# PowerManagementModule.net
KiCad netlist of a schematic drawn in Altium Designer
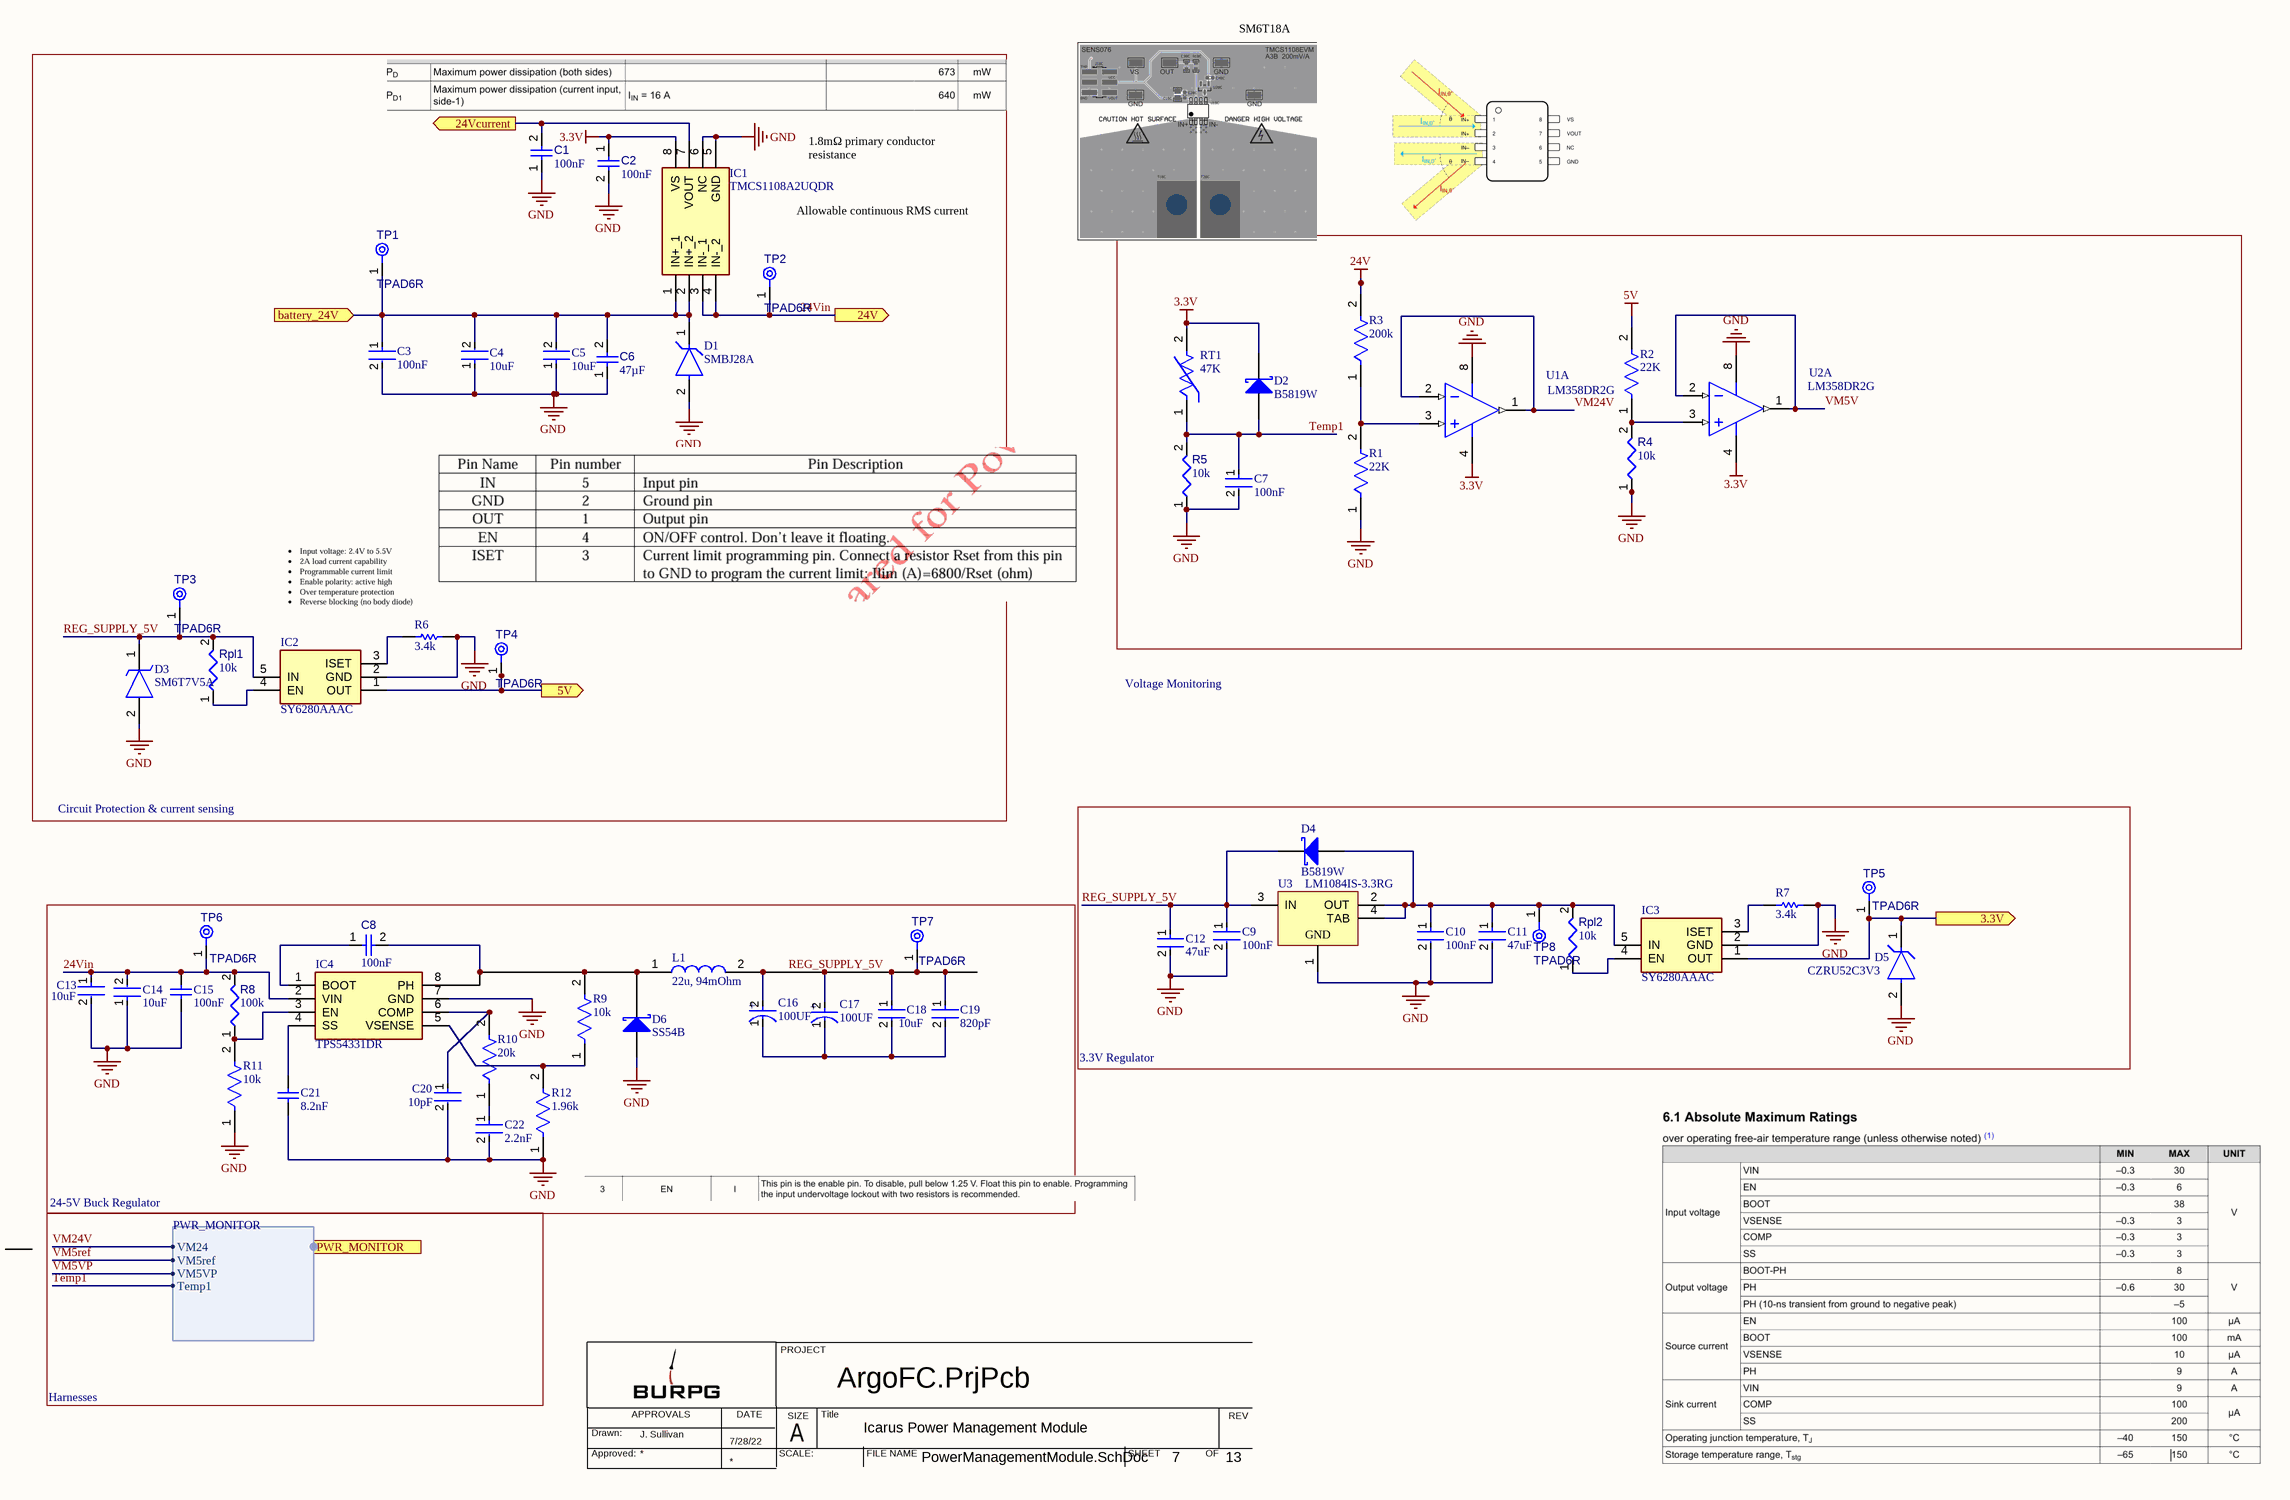
[diagram p0: PowerManagementModule.SchDoc]

(export (version "E")
  (design (tool "Eeschema 10.0.6"))
  (components
    (comp (ref "C1")
      (value "100nF")
      (footprint "CAPC1005X56X25LL10T15")
      (description "Chip Capacitor, 0.1 uF, +/- 5%, 16 V, 0402 (1005 Metric)")
      (fields (field (name "TOLERANCE") "5%") (field (name "Comment") "Capacitor 0.1 uF +/- 5% 16 V 0402"))
      (libsource (lib "Yuxuan chen") (part "CAP-NP-2"))
    )
    (comp (ref "C2")
      (value "100nF")
      (footprint "CAPC1005X56X25LL10T15")
      (description "Chip Capacitor, 0.1 uF, +/- 5%, 16 V, 0402 (1005 Metric)")
      (fields (field (name "TOLERANCE") "5%") (field (name "Comment") "Capacitor 0.1 uF +/- 5% 16 V 0402"))
      (libsource (lib "Yuxuan chen") (part "CAP-NP-2"))
    )
    (comp (ref "C3")
      (value "100nF")
      (footprint "FP-CGA3E-0_3-0_1-IPC_A")
      (description "Cap Ceramic 100nF 50V X7R 10% Pad SMD 0603 +125°C Automotive T/R")
      (fields (field (name "TOLERANCE") "10%") (field (name "VOLTAGE") "50V"))
      (libsource (lib "Altium Content Vault") (part "b4654b650e69147ec39a6b967a45e02"))
    )
    (comp (ref "C4")
      (value "10uF")
      (footprint "FP-GRM31-0_2-MFG")
      (description "CAP CER 10UF 50V X5R 1206")
      (fields
        (field (name "OCTOPART") "https://octopart.com/grm31cr61h106ka12l-murata-18903335")
        (field (name "TOLERANCE") "10%")
      )
      (libsource (lib "Altium Content Vault") (part "11868f565c42a9108669ba33697ecf6"))
    )
    (comp (ref "C5")
      (value "10uF")
      (footprint "FP-GRM31-0_2-MFG")
      (description "CAP CER 10UF 50V X5R 1206")
      (fields
        (field (name "OCTOPART") "https://octopart.com/grm31cr61h106ka12l-murata-18903335")
        (field (name "TOLERANCE") "10%")
      )
      (libsource (lib "Altium Content Vault") (part "11868f565c42a9108669ba33697ecf6"))
    )
    (comp (ref "C6")
      (value "47µF")
      (footprint "CAPC0805(2012)145_L")
      (description "Chip Capacitor, 47µF +/-40%, 50V, 0805, Thickness 1.45 mm")
      (fields (field (name "TOLERANCE") "10%") (field (name "Comment") "Capacitor 47µF +/-40% 6.3V 0805"))
      (libsource (lib "Yuxuan chen") (part "CAP-NP-2"))
    )
    (comp (ref "C7")
      (value "100nF")
      (footprint "FP-CGA3E-0_3-0_1-IPC_A")
      (description "Cap Ceramic 100nF 50V X7R 10% Pad SMD 0603 +125°C Automotive T/R")
      (fields (field (name "TOLERANCE") "10%") (field (name "VOLTAGE") "50V"))
      (libsource (lib "Altium Content Vault") (part "b4654b650e69147ec39a6b967a45e02"))
    )
    (comp (ref "C8")
      (value "100nF")
      (footprint "CAPC1608X90X40NL10T20")
      (description "Chip Capacitor, 100 nF, +/- 10%, 50 V, 0603 (1608 Metric)")
      (fields (field (name "TOLERANCE") "10%") (field (name "Comment") "Capacitor 100 nF +/-10% 50 V 0603"))
      (libsource (lib "Yuxuan chen") (part "CAP-NP-2"))
    )
    (comp (ref "C9")
      (value "100nF")
      (footprint "FP-CGA3E-0_3-0_1-IPC_A")
      (description "Cap Ceramic 100nF 50V X7R 10% Pad SMD 0603 +125°C Automotive T/R")
      (fields (field (name "TOLERANCE") "10%") (field (name "VOLTAGE") "50V"))
      (libsource (lib "Altium Content Vault") (part "b4654b650e69147ec39a6b967a45e02"))
    )
    (comp (ref "C10")
      (value "100nF")
      (footprint "FP-CGA3E-0_3-0_1-IPC_A")
      (description "Cap Ceramic 100nF 50V X7R 10% Pad SMD 0603 +125°C Automotive T/R")
      (fields (field (name "TOLERANCE") "10%") (field (name "VOLTAGE") "50V"))
      (libsource (lib "Altium Content Vault") (part "b4654b650e69147ec39a6b967a45e02"))
    )
    (comp (ref "C11")
      (value "47uF")
      (footprint "FP-C1210C476M4PACTU-MFG")
      (description "CAP CER 47UF 16V X5R 1210")
      (fields (field (name "TOLERANCE") "20%") (field (name "VOLTAGE") "16V"))
      (libsource (lib "Altium Content Vault") (part "02cd4be3c70576c341d710602a673aa"))
    )
    (comp (ref "C12")
      (value "47uF")
      (footprint "FP-C1210C476M4PACTU-MFG")
      (description "CAP CER 47UF 16V X5R 1210")
      (fields (field (name "TOLERANCE") "20%") (field (name "VOLTAGE") "16V"))
      (libsource (lib "Altium Content Vault") (part "02cd4be3c70576c341d710602a673aa"))
    )
    (comp (ref "C13")
      (value "10uF")
      (footprint "FP-GRM31-0_2-MFG")
      (description "CAP CER 10UF 50V X5R 1206")
      (fields
        (field (name "OCTOPART") "https://octopart.com/grm31cr61h106ka12l-murata-18903335")
        (field (name "TOLERANCE") "10%")
      )
      (libsource (lib "Altium Content Vault") (part "11868f565c42a9108669ba33697ecf6"))
    )
    (comp (ref "C14")
      (value "10uF")
      (footprint "FP-GRM31-0_2-MFG")
      (description "CAP CER 10UF 50V X5R 1206")
      (fields
        (field (name "OCTOPART") "https://octopart.com/grm31cr61h106ka12l-murata-18903335")
        (field (name "TOLERANCE") "10%")
      )
      (libsource (lib "Altium Content Vault") (part "11868f565c42a9108669ba33697ecf6"))
    )
    (comp (ref "C15")
      (value "100nF")
      (footprint "CAPC2013X100X50NL20T25")
      (description "C0805F103K5RACTU 10000 pF ±10% 50V Ceramic Capacitor X7R 0805 (2012 Metric)")
      (fields (field (name "PART NUMBER") "C0805F103K5RACTU") (field (name "MANUFACTURER") "Kemet"))
      (libsource (lib "Altium Content Vault") (part "CAP"))
    )
    (comp (ref "C16")
      (value "100UF")
      (footprint "FP-TPSC-MFG")
      (description "CAP TANT 100UF 10% 25V 2312")
      (fields (field (name "VOLTAGE") "10V") (field (name "TOLERANCE") "10%"))
      (libsource (lib "Altium Content Vault") (part "cf48714ba7e38822c1575c7ec0b6d1f"))
    )
    (comp (ref "C17")
      (value "100UF")
      (footprint "FP-TPSC-MFG")
      (description "CAP TANT 100UF 10% 25V 2312")
      (fields (field (name "VOLTAGE") "10V") (field (name "TOLERANCE") "10%"))
      (libsource (lib "Altium Content Vault") (part "cf48714ba7e38822c1575c7ec0b6d1f"))
    )
    (comp (ref "C18")
      (value "10uF")
      (footprint "FP-GRM21B-0_1-IPC_C")
      (description "Chip Multilayer Ceramic Capacitors for General Purpose, 0805, 10uF, X5R, 15%, 10%, 25V")
      (fields (field (name "TOLERANCE") "10%") (field (name "VOLTAGE") "16V"))
      (libsource (lib "Altium Content Vault") (part "b4654b650e69147ec39a6b967a45e02"))
    )
    (comp (ref "C19")
      (value "820pF")
      (footprint "FP-C0603C-CF-MFG")
      (description "C0603C 820pF Ceramic Multilayer Capacitor; 50 VDC; +125degC; X7R Dielec; +/-10%")
      (fields
        (field (name "TOLERANCE") "0.1")
        (field (name "OCTOPART") "https://octopart.com/c0603c821k5ractu-kemet-129686")
      )
      (libsource (lib "Altium Content Vault") (part "b4654b650e69147ec39a6b967a45e02"))
    )
    (comp (ref "C20")
      (value "10pF")
      (footprint "FP-C0805C-DN-MFG")
      (description "CAP CER 10PF 50V 10% NP0 0805C0805C100K5GACTU")
      (fields
        (field (name "MANUFACTURER PART NUMBER") "C0805C100K5GACTU")
        (field (name "MANUFACTURER") "KEMET")
      )
      (libsource (lib "Altium Content Vault") (part "b4654b650e69147ec39a6b967a45e02"))
    )
    (comp (ref "C21")
      (value "8.2nF")
      (footprint "CAPC1005X55X25NL05T10")
      (description "GRM155R71C822KA01D 0402  8.2nF")
      (fields (field (name "PART NUMBER") "GRM155R71C822KA01D") (field (name "MANUFACTURER") "Murata"))
      (libsource (lib "Altium Content Vault") (part "CAP"))
    )
    (comp (ref "C22")
      (value "2.2nF")
      (footprint "FP-CL21-IPC_C")
      (description "CL21 Series 0805 2.2nF 50V ±5% Tolerance C0G Multilayer Ceramic Chip Capacitor CL21C222JBFNNNE")
      (fields (field (name "TOLERANCE") "5%") (field (name "VOLTAGE") "50V"))
      (libsource (lib "Altium Content Vault") (part "b4654b650e69147ec39a6b967a45e02"))
    )
    (comp (ref "D1")
      (value "SMBJ28A")
      (footprint "FP-SMBJ-MFG")
      (description "TVS DIODE 28V 45.4V DO214AA")
      (fields
        (field (name "MANUFACTURER") "Littelfuse Inc")
        (field (name "OCTOPART") "https://octopart.com/smbj28a-littelfuse-350790")
      )
      (libsource (lib "Altium Content Vault") (part "f813f71cba58e380607f5dd3caf9714"))
    )
    (comp (ref "D2")
      (value "B5819W")
      (footprint "MCC-SOD123_V")
      (description "Schottky Barrier Rectifier, 40 V, 1 A, -65 to 125 degC, 2-Pin SOD123, RoHS, Tape and Reel")
      (fields (field (name "MANUFACTURER") "Micro Commercial Components"))
      (libsource (lib "Yuxuan chen") (part "DSKY-AK-2"))
    )
    (comp (ref "D3")
      (value "SM6T7V5A")
      (footprint "SamacSys:DIOM5436X265N")
      (description "TVS Diode (Uni-directional)")
      (fields (field (name "MOUSER PART NUMBER") "511-SM6T7V5A"))
      (libsource (lib "*") (part "SM6T7V5A"))
    )
    (comp (ref "D4")
      (value "B5819W")
      (footprint "MCC-SOD123_V")
      (description "Schottky Barrier Rectifier, 40 V, 1 A, -65 to 125 degC, 2-Pin SOD123, RoHS, Tape and Reel")
      (fields (field (name "MANUFACTURER") "Micro Commercial Components"))
      (libsource (lib "Yuxuan chen") (part "DSKY-AK-2"))
    )
    (comp (ref "D5")
      (value "CZRU52C3V3")
      (footprint "FP-0603-SOD-523F-MFG")
      (description "DIODE ZENER 3.3V 150MW 0603")
      (fields (field (name "TOLERANCE") "5%"))
      (libsource (lib "Altium Content Vault") (part "f813f71cba58e380607f5dd3caf9714"))
    )
    (comp (ref "D6")
      (value "SS54B")
      (footprint "JCET-SMB-2_M")
      (description "Schottky Barrier Rectifier, 40 V, 5 A, -55 to 150 degC, 2-Pin SMD")
      (fields (field (name "MANUFACTURER") "JCET"))
      (libsource (lib "Yuxuan chen") (part "DSKY-AK-2"))
    )
    (comp (ref "IC1")
      (value "TMCS1108A2UQDR")
      (footprint "SamacSys:SOIC127P600X175-8N")
      (fields (field (name "MOUSER PART NUMBER") "595-TMCS1108A2UQDR"))
      (libsource (lib "*") (part "TMCS1108A2UQDR"))
    )
    (comp (ref "IC2")
      (value "SY6280AAAC")
      (footprint "SamacSys:SOT95P285X140-5N")
      (description "Integrated Circuit")
      (libsource (lib "*") (part "SY6280AAAC"))
    )
    (comp (ref "IC3")
      (value "SY6280AAAC")
      (footprint "SamacSys:SOT95P285X140-5N")
      (description "Integrated Circuit")
      (libsource (lib "*") (part "SY6280AAAC"))
    )
    (comp (ref "IC4")
      (value "TPS54331DR")
      (footprint "SamacSys:SOIC127P600X175-8N")
      (description "Integrated Circuit")
      (fields (field (name "MOUSER PART NUMBER") "595-TPS54331DR"))
      (libsource (lib "*") (part "TPS54331DR"))
    )
    (comp (ref "L1")
      (value "22u, 94mOhm")
      (footprint "SamacSys:INDPM8682X400N")
      (description "Inductor， IHLP3232DZER220M11, 3.3A sat")
      (fields
        (field (name "MANUFACTURER_PART_NUMBER") "IHLP3232DZER220M11")
        (field (name "MOUSER PART NUMBER") "70-IHLP3232DZER220M1")
      )
      (libsource (lib "*") (part "IHLP3232DZER220M11"))
    )
    (comp (ref "R1")
      (value "22K")
      (footprint "FP-CRCW0603-e3-IPC_B")
      (description "RES Thick Film, 22kΩ, 1%, 0.1W, 100ppm/°C, 0603")
      (fields (field (name "TOLERANCE") "1%"))
      (libsource (lib "Altium Content Vault") (part "1029c3af85768c4190bb7ad29bc67b5"))
    )
    (comp (ref "R2")
      (value "22K")
      (footprint "FP-CRCW0603-e3-IPC_B")
      (description "RES Thick Film, 22kΩ, 1%, 0.1W, 100ppm/°C, 0603")
      (fields (field (name "TOLERANCE") "1%"))
      (libsource (lib "Altium Content Vault") (part "1029c3af85768c4190bb7ad29bc67b5"))
    )
    (comp (ref "R3")
      (value "200k")
      (footprint "FP-RC0603-0_55-IPC_B")
      (description "RES SMD 200K OHM 1% 1/10W 0603")
      (fields (field (name "TOLERANCE") "1%"))
      (libsource (lib "Altium Content Vault") (part "1029c3af85768c4190bb7ad29bc67b5"))
    )
    (comp (ref "R4")
      (value "10k")
      (footprint "RESC0402(1005)_L")
      (description "10K 0.063W 1% 0402 (1005 Metric)  SMD")
      (fields (field (name "POWER") "63mW") (field (name "TOLERANCE") "1%"))
      (libsource (lib "Yuxuan chen") (part "10KR2F"))
    )
    (comp (ref "R5")
      (value "10k")
      (footprint "RESC0402(1005)_L")
      (description "10K 0.063W 1% 0402 (1005 Metric)  SMD")
      (fields (field (name "POWER") "63mW") (field (name "TOLERANCE") "1%"))
      (libsource (lib "Yuxuan chen") (part "10KR2F"))
    )
    (comp (ref "R6")
      (value "3.4k")
      (footprint "RESC1609X50X30LL10T20")
      (fields (field (name "MANUFACTURER") "Vishay Dale") (field (name "PART NUMBER") "CRCW06033K40FKEA"))
      (libsource (lib "Altium Content Vault") (part "RES"))
    )
    (comp (ref "R7")
      (value "3.4k")
      (footprint "RESC1609X50X30LL10T20")
      (fields (field (name "MANUFACTURER") "Vishay Dale") (field (name "PART NUMBER") "CRCW06033K40FKEA"))
      (libsource (lib "Altium Content Vault") (part "RES"))
    )
    (comp (ref "R8")
      (value "100k")
      (footprint "RESC1608X55X25ML10T15")
      (description "Chip Resistor, 100 KOhm, +/- 1%, 0.1 W, -55 to 155 degC, 0603 (1608 Metric)")
      (fields (field (name "TOLERANCE") "1%") (field (name "POWER") "100mW"))
      (libsource (lib "Yuxuan chen") (part "RES-2"))
    )
    (comp (ref "R9")
      (value "10k")
      (footprint "FP-CRCW0805-e3-IPC_A")
      (description "RES Thick Film, 10kΩ, 1%, 0.125W, 100ppm/°C, 0805")
      (fields (field (name "TOLERANCE") "1%"))
      (libsource (lib "Altium Content Vault") (part "1029c3af85768c4190bb7ad29bc67b5"))
    )
    (comp (ref "R10")
      (value "20k")
      (footprint "FP-CRCW0402-e3-IPC_B")
      (description "RES Thick Film, 20kΩ, 1%, 0.063W, 100ppm/°C, 0402")
      (fields (field (name "TOLERANCE") "1%"))
      (libsource (lib "Altium Content Vault") (part "1029c3af85768c4190bb7ad29bc67b5"))
    )
    (comp (ref "R11")
      (value "10k")
      (footprint "FP-CRCW0805-e3-IPC_A")
      (description "RES Thick Film, 10kΩ, 1%, 0.125W, 100ppm/°C, 0805")
      (fields (field (name "TOLERANCE") "1%"))
      (libsource (lib "Altium Content Vault") (part "1029c3af85768c4190bb7ad29bc67b5"))
    )
    (comp (ref "R12")
      (value "1.96k")
      (footprint "FP-CRCW0402-e3-MFG")
      (description "CRCW04021K96FKED  RES Thick Film, 1.96kΩ, 1%, 0.063W, 100ppm/°C, 0402")
      (fields (field (name "TOLERANCE") "1%"))
      (libsource (lib "Altium Content Vault") (part "1029c3af85768c4190bb7ad29bc67b5"))
    )
    (comp (ref "Rpl1")
      (value "10k")
      (footprint "RESC0402(1005)_L")
      (description "10K 0.063W 1% 0402 (1005 Metric)  SMD")
      (fields (field (name "POWER") "63mW") (field (name "TOLERANCE") "1%"))
      (libsource (lib "Yuxuan chen") (part "10KR2F"))
    )
    (comp (ref "Rpl2")
      (value "10k")
      (footprint "RESC0402(1005)_L")
      (description "10K 0.063W 1% 0402 (1005 Metric)  SMD")
      (fields (field (name "POWER") "63mW") (field (name "TOLERANCE") "1%"))
      (libsource (lib "Yuxuan chen") (part "10KR2F"))
    )
    (comp (ref "RT1")
      (value "47K")
      (footprint "FP-NCP18-0_15-IPC_A")
      (description "NTC Thermistor for Temperature Sensor, 0603, 47kΩ, 5%, 0.046mA, 5V")
      (fields (field (name "TOLERANCE") "5%"))
      (libsource (lib "Altium Content Vault") (part "3b148a6ebabc5fb4d708a66c052d352"))
    )
    (comp (ref "TP1")
      (value "TPAD6R")
      (footprint "TP06R")
      (description "0.6mm round")
      (libsource (lib "Yuxuan chen") (part "CMP-001-0001-4"))
    )
    (comp (ref "TP2")
      (value "TPAD6R")
      (footprint "TP06R")
      (description "0.6mm round")
      (libsource (lib "Yuxuan chen") (part "CMP-001-0001-4"))
    )
    (comp (ref "TP3")
      (value "TPAD6R")
      (footprint "TP06R")
      (description "0.6mm round")
      (libsource (lib "Yuxuan chen") (part "CMP-001-0001-4"))
    )
    (comp (ref "TP4")
      (value "TPAD6R")
      (footprint "TP06R")
      (description "0.6mm round")
      (libsource (lib "Yuxuan chen") (part "CMP-001-0001-4"))
    )
    (comp (ref "TP5")
      (value "TPAD6R")
      (footprint "TP06R")
      (description "0.6mm round")
      (libsource (lib "Yuxuan chen") (part "CMP-001-0001-4"))
    )
    (comp (ref "TP6")
      (value "TPAD6R")
      (footprint "TP06R")
      (description "0.6mm round")
      (libsource (lib "Yuxuan chen") (part "CMP-001-0001-4"))
    )
    (comp (ref "TP7")
      (value "TPAD6R")
      (footprint "TP06R")
      (description "0.6mm round")
      (libsource (lib "Yuxuan chen") (part "CMP-001-0001-4"))
    )
    (comp (ref "TP8")
      (value "TPAD6R")
      (footprint "TP06R")
      (description "0.6mm round")
      (libsource (lib "Yuxuan chen") (part "CMP-001-0001-4"))
    )
    (comp (ref "U1")
      (value "LM358DR2G")
      (footprint "ONSC-SOIC-8-751-07_V")
      (fields (field (name "MANUFACTURER") "ON Semiconductor"))
      (libsource (lib "Yuxuan chen") (part "ONSC-LM258_2904-8"))
    )
    (comp (ref "U2")
      (value "LM358DR2G")
      (footprint "ONSC-SOIC-8-751-07_V")
      (fields (field (name "MANUFACTURER") "ON Semiconductor"))
      (libsource (lib "Yuxuan chen") (part "ONSC-LM258_2904-8"))
    )
    (comp (ref "U3")
      (value "LM1084IS-3.3RG")
      (footprint "KTT0003B_N")
      (description "5A Low Dropout Positive Regulators, 3-pin TO-263, Pb-Free")
      (fields
        (field (name "PARTNUMBER") "LM1084IS-3.3/NOPB")
        (field (name "MANUFACTURER") "Texas Instruments")
      )
      (libsource (lib "Altium Content Vault") (part "PM-REG-LM1086-SOT4"))
    )
  )
  (nets
    (net (code "2") (name "/24Vcurrent") (class "Default")
      (node (ref "C1") (pin "2") (pinfunction "2_2") (pintype "passive"))
      (node (ref "IC1") (pin "7") (pinfunction "VOUT_7") (pintype "passive"))
    )
    (net (code "3") (name "/REG_SUPPLY_5V") (class "Default")
      (node (ref "C12") (pin "1") (pinfunction "1_1") (pintype "passive"))
      (node (ref "C16") (pin "2") (pinfunction "A_2") (pintype "passive"))
      (node (ref "C17") (pin "2") (pinfunction "A_2") (pintype "passive"))
      (node (ref "C18") (pin "1") (pinfunction "1_1") (pintype "passive"))
      (node (ref "C19") (pin "1") (pinfunction "1_1") (pintype "passive"))
      (node (ref "C9") (pin "1") (pinfunction "1_1") (pintype "passive"))
      (node (ref "D3") (pin "1") (pinfunction "K_1") (pintype "passive"))
      (node (ref "D4") (pin "2") (pinfunction "K_2") (pintype "passive"))
      (node (ref "IC2") (pin "5") (pinfunction "IN_5") (pintype "passive"))
      (node (ref "L1") (pin "2") (pinfunction "2_2") (pintype "passive"))
      (node (ref "Rpl1") (pin "2") (pinfunction "2_2") (pintype "passive"))
      (node (ref "TP3") (pin "1") (pinfunction "TP_1") (pintype "passive"))
      (node (ref "TP7") (pin "1") (pinfunction "TP_1") (pintype "passive"))
      (node (ref "U3") (pin "3") (pinfunction "IN_3") (pintype "power_in"))
    )
    (net (code "4") (name "/Temp1") (class "Default")
      (node (ref "C7") (pin "1") (pinfunction "1_1") (pintype "passive"))
      (node (ref "D2") (pin "1") (pinfunction "A_1") (pintype "passive"))
      (node (ref "R5") (pin "2") (pinfunction "2_2") (pintype "passive"))
      (node (ref "RT1") (pin "1") (pinfunction "1_1") (pintype "passive"))
    )
    (net (code "5") (name "/VM5V") (class "Default")
      (node (ref "U2") (pin "1") (pinfunction "OUTA_1") (pintype "output"))
      (node (ref "U2") (pin "2") (pinfunction "INA-_2") (pintype "input"))
    )
    (net (code "8") (name "/VM24V") (class "Default")
      (node (ref "U1") (pin "1") (pinfunction "OUTA_1") (pintype "output"))
      (node (ref "U1") (pin "2") (pinfunction "INA-_2") (pintype "input"))
    )
    (net (code "9") (name "/battery_24V") (class "Default")
      (node (ref "C3") (pin "1") (pinfunction "1_1") (pintype "passive"))
      (node (ref "C4") (pin "2") (pinfunction "2_2") (pintype "passive"))
      (node (ref "C5") (pin "2") (pinfunction "2_2") (pintype "passive"))
      (node (ref "C6") (pin "2") (pinfunction "2_2") (pintype "passive"))
      (node (ref "D1") (pin "1") (pinfunction "C_1") (pintype "passive"))
      (node (ref "IC1") (pin "1") (pinfunction "IN+_1_1") (pintype "passive"))
      (node (ref "IC1") (pin "2") (pinfunction "IN+_2_2") (pintype "passive"))
      (node (ref "TP1") (pin "1") (pinfunction "TP_1") (pintype "passive"))
    )
    (net (code "11") (name "3.3V") (class "Default")
      (node (ref "C2") (pin "1") (pinfunction "1_1") (pintype "passive"))
      (node (ref "D2") (pin "2") (pinfunction "K_2") (pintype "passive"))
      (node (ref "D5") (pin "1") (pinfunction "C_1") (pintype "passive"))
      (node (ref "IC1") (pin "8") (pinfunction "VS_8") (pintype "passive"))
      (node (ref "IC3") (pin "1") (pinfunction "OUT_1") (pintype "passive"))
      (node (ref "RT1") (pin "2") (pinfunction "2_2") (pintype "passive"))
      (node (ref "TP5") (pin "1") (pinfunction "TP_1") (pintype "passive"))
      (node (ref "U1") (pin "4") (pinfunction "VEE/GND_4") (pintype "power_in"))
      (node (ref "U2") (pin "4") (pinfunction "VEE/GND_4") (pintype "power_in"))
    )
    (net (code "12") (name "5V") (class "Default")
      (node (ref "IC2") (pin "1") (pinfunction "OUT_1") (pintype "passive"))
      (node (ref "R2") (pin "2") (pinfunction "2_2") (pintype "passive"))
      (node (ref "TP4") (pin "1") (pinfunction "TP_1") (pintype "passive"))
    )
    (net (code "13") (name "24V") (class "Default")
      (node (ref "C13") (pin "1") (pinfunction "1_1") (pintype "passive"))
      (node (ref "C14") (pin "2") (pinfunction "2_2") (pintype "passive"))
      (node (ref "C15") (pin "2") (pinfunction "2_2") (pintype "passive"))
      (node (ref "IC1") (pin "3") (pinfunction "IN-_1_3") (pintype "passive"))
      (node (ref "IC1") (pin "4") (pinfunction "IN-_2_4") (pintype "passive"))
      (node (ref "IC4") (pin "2") (pinfunction "VIN_2") (pintype "passive"))
      (node (ref "R3") (pin "2") (pinfunction "2_2") (pintype "passive"))
      (node (ref "R8") (pin "2") (pinfunction "2_2") (pintype "passive"))
      (node (ref "TP2") (pin "1") (pinfunction "TP_1") (pintype "passive"))
      (node (ref "TP6") (pin "1") (pinfunction "TP_1") (pintype "passive"))
    )
    (net (code "14") (name "GND") (class "Default")
      (node (ref "C1") (pin "1") (pinfunction "1_1") (pintype "passive"))
      (node (ref "C10") (pin "2") (pinfunction "2_2") (pintype "passive"))
      (node (ref "C11") (pin "2") (pinfunction "2_2") (pintype "passive"))
      (node (ref "C12") (pin "2") (pinfunction "2_2") (pintype "passive"))
      (node (ref "C13") (pin "2") (pinfunction "2_2") (pintype "passive"))
      (node (ref "C14") (pin "1") (pinfunction "1_1") (pintype "passive"))
      (node (ref "C15") (pin "1") (pinfunction "1_1") (pintype "passive"))
      (node (ref "C2") (pin "2") (pinfunction "2_2") (pintype "passive"))
      (node (ref "C20") (pin "2") (pinfunction "2_2") (pintype "passive"))
      (node (ref "C21") (pin "1") (pinfunction "1_1") (pintype "passive"))
      (node (ref "C22") (pin "2") (pinfunction "2_2") (pintype "passive"))
      (node (ref "C3") (pin "2") (pinfunction "2_2") (pintype "passive"))
      (node (ref "C4") (pin "1") (pinfunction "1_1") (pintype "passive"))
      (node (ref "C5") (pin "1") (pinfunction "1_1") (pintype "passive"))
      (node (ref "C6") (pin "1") (pinfunction "1_1") (pintype "passive"))
      (node (ref "C7") (pin "2") (pinfunction "2_2") (pintype "passive"))
      (node (ref "C9") (pin "2") (pinfunction "2_2") (pintype "passive"))
      (node (ref "D1") (pin "2") (pinfunction "A_2") (pintype "passive"))
      (node (ref "D3") (pin "2") (pinfunction "A_2") (pintype "passive"))
      (node (ref "D5") (pin "2") (pinfunction "A_2") (pintype "passive"))
      (node (ref "D6") (pin "1") (pinfunction "A_1") (pintype "passive"))
      (node (ref "IC1") (pin "5") (pinfunction "GND_5") (pintype "passive"))
      (node (ref "IC1") (pin "6") (pinfunction "NC_6") (pintype "passive"))
      (node (ref "IC2") (pin "2") (pinfunction "GND_2") (pintype "passive"))
      (node (ref "IC3") (pin "2") (pinfunction "GND_2") (pintype "passive"))
      (node (ref "IC4") (pin "7") (pinfunction "GND_7") (pintype "passive"))
      (node (ref "R1") (pin "1") (pinfunction "1_1") (pintype "passive"))
      (node (ref "R11") (pin "1") (pinfunction "1_1") (pintype "passive"))
      (node (ref "R12") (pin "1") (pinfunction "1_1") (pintype "passive"))
      (node (ref "R4") (pin "1") (pinfunction "1_1") (pintype "passive"))
      (node (ref "R5") (pin "1") (pinfunction "1_1") (pintype "passive"))
      (node (ref "R6") (pin "2") (pinfunction "2_2") (pintype "passive"))
      (node (ref "R7") (pin "2") (pinfunction "2_2") (pintype "passive"))
      (node (ref "U1") (pin "8") (pinfunction "VCC_8") (pintype "power_in"))
      (node (ref "U2") (pin "8") (pinfunction "VCC_8") (pintype "power_in"))
      (node (ref "U3") (pin "1") (pinfunction "GND_1") (pintype "power_in"))
    )
    (net (code "15") (name "Net-(C16-C)") (class "Default")
      (node (ref "C16") (pin "1") (pinfunction "C_1") (pintype "passive"))
      (node (ref "C17") (pin "1") (pinfunction "C_1") (pintype "passive"))
      (node (ref "C18") (pin "2") (pinfunction "2_2") (pintype "passive"))
      (node (ref "C19") (pin "2") (pinfunction "2_2") (pintype "passive"))
    )
    (net (code "16") (name "Net-(C22-Pad1)") (class "Default")
      (node (ref "C22") (pin "1") (pinfunction "1_1") (pintype "passive"))
      (node (ref "R10") (pin "1") (pinfunction "1_1") (pintype "passive"))
    )
    (net (code "17") (name "Net-(D4-A)") (class "Default")
      (node (ref "C10") (pin "1") (pinfunction "1_1") (pintype "passive"))
      (node (ref "C11") (pin "1") (pinfunction "1_1") (pintype "passive"))
      (node (ref "D4") (pin "1") (pinfunction "A_1") (pintype "passive"))
      (node (ref "IC3") (pin "5") (pinfunction "IN_5") (pintype "passive"))
      (node (ref "Rpl2") (pin "2") (pinfunction "2_2") (pintype "passive"))
      (node (ref "TP8") (pin "1") (pinfunction "TP_1") (pintype "passive"))
      (node (ref "U3") (pin "2") (pinfunction "OUT_2") (pintype "power_in"))
      (node (ref "U3") (pin "4") (pinfunction "TAB_4") (pintype "power_in"))
    )
    (net (code "18") (name "Net-(D6-K)") (class "Default")
      (node (ref "C8") (pin "2") (pinfunction "2_2") (pintype "passive"))
      (node (ref "D6") (pin "2") (pinfunction "K_2") (pintype "passive"))
      (node (ref "IC4") (pin "8") (pinfunction "PH_8") (pintype "passive"))
      (node (ref "L1") (pin "1") (pinfunction "1_1") (pintype "passive"))
      (node (ref "R9") (pin "2") (pinfunction "2_2") (pintype "passive"))
    )
    (net (code "19") (name "Net-(IC2-EN)") (class "Default")
      (node (ref "IC2") (pin "4") (pinfunction "EN_4") (pintype "passive"))
      (node (ref "Rpl1") (pin "1") (pinfunction "1_1") (pintype "passive"))
    )
    (net (code "20") (name "Net-(IC2-ISET)") (class "Default")
      (node (ref "IC2") (pin "3") (pinfunction "ISET_3") (pintype "passive"))
      (node (ref "R6") (pin "1") (pinfunction "1_1") (pintype "passive"))
    )
    (net (code "21") (name "Net-(IC3-EN)") (class "Default")
      (node (ref "IC3") (pin "4") (pinfunction "EN_4") (pintype "passive"))
      (node (ref "Rpl2") (pin "1") (pinfunction "1_1") (pintype "passive"))
    )
    (net (code "22") (name "Net-(IC3-ISET)") (class "Default")
      (node (ref "IC3") (pin "3") (pinfunction "ISET_3") (pintype "passive"))
      (node (ref "R7") (pin "1") (pinfunction "1_1") (pintype "passive"))
    )
    (net (code "23") (name "Net-(IC4-BOOT)") (class "Default")
      (node (ref "C8") (pin "1") (pinfunction "1_1") (pintype "passive"))
      (node (ref "IC4") (pin "1") (pinfunction "BOOT_1") (pintype "passive"))
    )
    (net (code "24") (name "Net-(IC4-COMP)") (class "Default")
      (node (ref "C20") (pin "1") (pinfunction "1_1") (pintype "passive"))
      (node (ref "IC4") (pin "6") (pinfunction "COMP_6") (pintype "passive"))
      (node (ref "R10") (pin "2") (pinfunction "2_2") (pintype "passive"))
    )
    (net (code "25") (name "Net-(IC4-EN)") (class "Default")
      (node (ref "IC4") (pin "3") (pinfunction "EN_3") (pintype "passive"))
      (node (ref "R11") (pin "2") (pinfunction "2_2") (pintype "passive"))
      (node (ref "R8") (pin "1") (pinfunction "1_1") (pintype "passive"))
    )
    (net (code "26") (name "Net-(IC4-SS)") (class "Default")
      (node (ref "C21") (pin "2") (pinfunction "2_2") (pintype "passive"))
      (node (ref "IC4") (pin "4") (pinfunction "SS_4") (pintype "passive"))
    )
    (net (code "27") (name "Net-(IC4-VSENSE)") (class "Default")
      (node (ref "IC4") (pin "5") (pinfunction "VSENSE_5") (pintype "passive"))
      (node (ref "R12") (pin "2") (pinfunction "2_2") (pintype "passive"))
      (node (ref "R9") (pin "1") (pinfunction "1_1") (pintype "passive"))
    )
    (net (code "28") (name "Net-(U1A-INA+)") (class "Default")
      (node (ref "R1") (pin "2") (pinfunction "2_2") (pintype "passive"))
      (node (ref "R3") (pin "1") (pinfunction "1_1") (pintype "passive"))
      (node (ref "U1") (pin "3") (pinfunction "INA+_3") (pintype "input"))
    )
    (net (code "29") (name "Net-(U2A-INA+)") (class "Default")
      (node (ref "R2") (pin "1") (pinfunction "1_1") (pintype "passive"))
      (node (ref "R4") (pin "2") (pinfunction "2_2") (pintype "passive"))
      (node (ref "U2") (pin "3") (pinfunction "INA+_3") (pintype "input"))
    )
  )
)
